# bicyclelab-charger-1.net
KiCad netlist of a schematic drawn in EAGLE
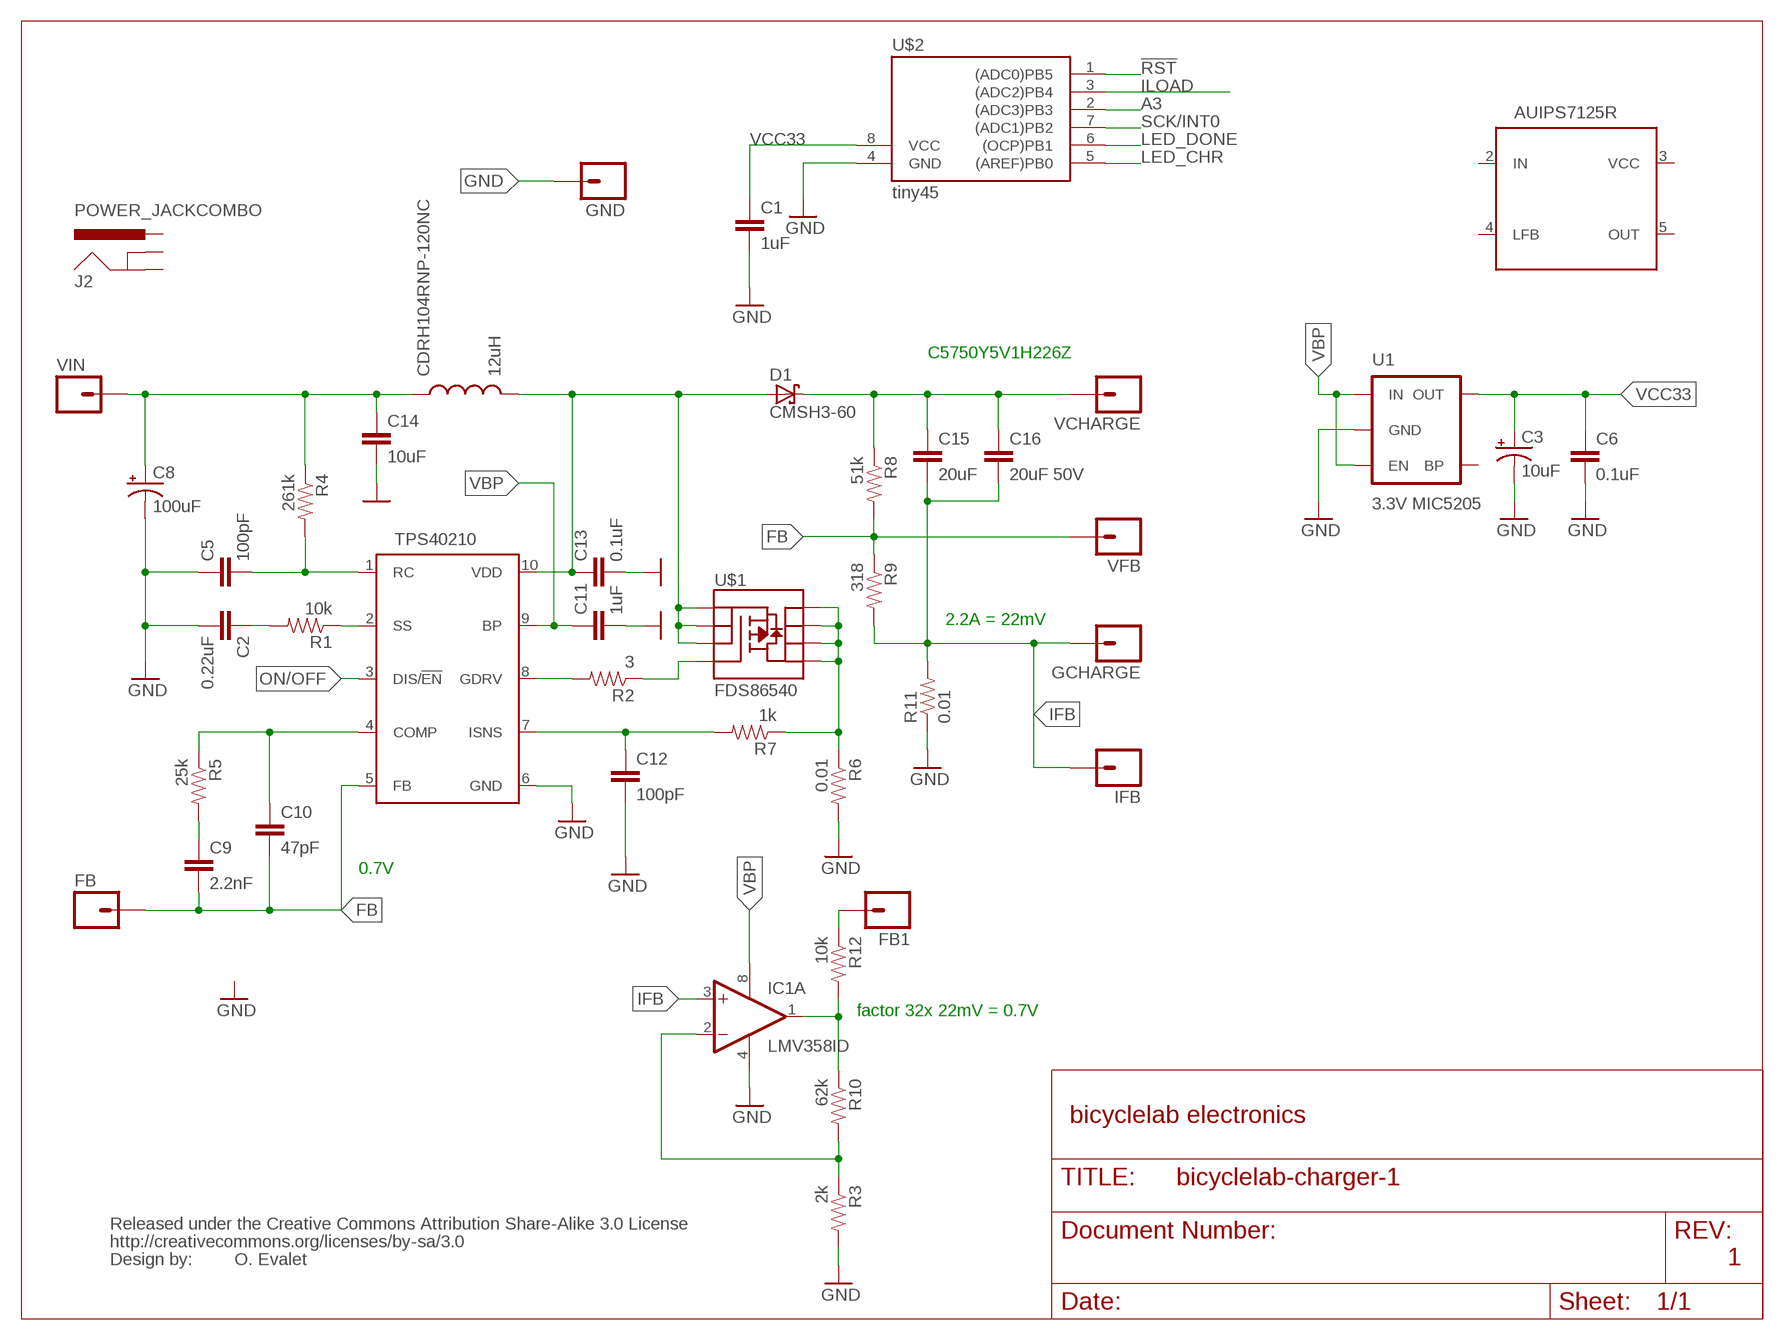
[diagram p0: schematic, sheet 1]

(export (version "E")
  (design (tool "Eeschema 10.0.6"))
  (components
    (comp (ref "11")
      (value "TPS40211")
      (footprint "eagle-import:MSOP-10-GNDPAD")
      (libsource (lib "eagle-import") (part "TPS40210"))
    )
    (comp (ref "C1")
      (value "1uF")
      (footprint "eagle-import:0402-CAP")
      (libsource (lib "eagle-import") (part "SparkFun_CAP0402-CAP"))
    )
    (comp (ref "C2")
      (value "0.22uF")
      (footprint "eagle-import:0402-CAP")
      (libsource (lib "eagle-import") (part "SparkFun_CAP0402-CAP"))
    )
    (comp (ref "C3")
      (value "10uF")
      (footprint "eagle-import:EIA3216")
      (libsource (lib "eagle-import") (part "SparkFun_CAP_POL1206"))
    )
    (comp (ref "C5")
      (value "100pF")
      (footprint "eagle-import:0402-CAP")
      (libsource (lib "eagle-import") (part "SparkFun_CAP0402-CAP"))
    )
    (comp (ref "C6")
      (value "0.1uF")
      (footprint "eagle-import:0603-CAP")
      (libsource (lib "eagle-import") (part "SparkFun_CAP0603-CAP"))
    )
    (comp (ref "C8")
      (value "100uF")
      (footprint "eagle-import:PANASONIC_C")
      (libsource (lib "eagle-import") (part "CAP_POLC"))
    )
    (comp (ref "C9")
      (value "2.2nF")
      (footprint "eagle-import:0402-CAP")
      (libsource (lib "eagle-import") (part "SparkFun_CAP0402-CAP"))
    )
    (comp (ref "C10")
      (value "47pF")
      (footprint "eagle-import:0402-CAP")
      (libsource (lib "eagle-import") (part "SparkFun_CAP0402-CAP"))
    )
    (comp (ref "C11")
      (value "1uF")
      (footprint "eagle-import:0402-CAP")
      (libsource (lib "eagle-import") (part "SparkFun_CAP0402-CAP"))
    )
    (comp (ref "C12")
      (value "100pF")
      (footprint "eagle-import:0402-CAP")
      (libsource (lib "eagle-import") (part "SparkFun_CAP0402-CAP"))
    )
    (comp (ref "C13")
      (value "0.1uF")
      (footprint "eagle-import:0402-CAP")
      (libsource (lib "eagle-import") (part "SparkFun_CAP0402-CAP"))
    )
    (comp (ref "C14")
      (value "10uF")
      (footprint "eagle-import:1206")
      (libsource (lib "eagle-import") (part "CAP1206"))
    )
    (comp (ref "C15")
      (value "20uF")
      (footprint "eagle-import:C2220K")
      (libsource (lib "eagle-import") (part "CAPCAP2220"))
    )
    (comp (ref "C16")
      (value "20uF 50V")
      (footprint "eagle-import:C2220K")
      (libsource (lib "eagle-import") (part "CAPCAP2220"))
    )
    (comp (ref "CDRH104RNP-120NC")
      (value "12uH")
      (footprint "eagle-import:CR75")
      (libsource (lib "eagle-import") (part "INDUCTORCR75"))
    )
    (comp (ref "D1")
      (value "CMSH3-60")
      (footprint "eagle-import:SMC")
      (libsource (lib "eagle-import") (part "MBRS30T32"))
    )
    (comp (ref "FB")
      (value "M01SMDNS")
      (footprint "eagle-import:1X01NS")
      (libsource (lib "eagle-import") (part "M01SMDNS"))
    )
    (comp (ref "FB1")
      (value "M01SMDNS")
      (footprint "eagle-import:1X01NS")
      (libsource (lib "eagle-import") (part "M01SMDNS"))
    )
    (comp (ref "GCHARGE")
      (value "M01SMDNS")
      (footprint "eagle-import:1X01NS")
      (libsource (lib "eagle-import") (part "M01SMDNS"))
    )
    (comp (ref "GND")
      (value "M01SMDNS")
      (footprint "eagle-import:1X01NS")
      (libsource (lib "eagle-import") (part "M01SMDNS"))
    )
    (comp (ref "IC1")
      (value "LMV358ID")
      (footprint "eagle-import:SO08")
      (libsource (lib "eagle-import") (part "MCP602SN"))
    )
    (comp (ref "IFB")
      (value "M01SMDNS")
      (footprint "eagle-import:1X01NS")
      (libsource (lib "eagle-import") (part "M01SMDNS"))
    )
    (comp (ref "J2")
      (value "POWER_JACKCOMBO")
      (footprint "eagle-import:POWER_JACK_COMBO")
      (libsource (lib "eagle-import") (part "POWER_JACKCOMBO"))
    )
    (comp (ref "R1")
      (value "10k")
      (footprint "eagle-import:0402-RES")
      (libsource (lib "eagle-import") (part "RESISTOR0402-RES"))
    )
    (comp (ref "R2")
      (value "3")
      (footprint "eagle-import:0402-RES")
      (libsource (lib "eagle-import") (part "RESISTOR0402-RES"))
    )
    (comp (ref "R3")
      (value "2k")
      (footprint "eagle-import:0402-RES")
      (libsource (lib "eagle-import") (part "RESISTOR0402-RES"))
    )
    (comp (ref "R4")
      (value "261k")
      (footprint "eagle-import:0402-RES")
      (libsource (lib "eagle-import") (part "RESISTOR0402-RES"))
    )
    (comp (ref "R5")
      (value "25k")
      (footprint "eagle-import:0402-RES")
      (libsource (lib "eagle-import") (part "RESISTOR0402-RES"))
    )
    (comp (ref "R6")
      (value "0.01")
      (footprint "eagle-import:0402-RES")
      (libsource (lib "eagle-import") (part "RESISTOR0402-RES"))
    )
    (comp (ref "R7")
      (value "1k")
      (footprint "eagle-import:0402-RES")
      (libsource (lib "eagle-import") (part "RESISTOR0402-RES"))
    )
    (comp (ref "R8")
      (value "51k")
      (footprint "eagle-import:0402-RES")
      (libsource (lib "eagle-import") (part "RESISTOR0402-RES"))
    )
    (comp (ref "R9")
      (value "318")
      (footprint "eagle-import:0402-RES")
      (libsource (lib "eagle-import") (part "RESISTOR0402-RES"))
    )
    (comp (ref "R10")
      (value "62k")
      (footprint "eagle-import:0402-RES")
      (libsource (lib "eagle-import") (part "RESISTOR0402-RES"))
    )
    (comp (ref "R11")
      (value "0.01")
      (footprint "eagle-import:0402-RES")
      (libsource (lib "eagle-import") (part "RESISTOR0402-RES"))
    )
    (comp (ref "R12")
      (value "10k")
      (footprint "eagle-import:0402-RES")
      (libsource (lib "eagle-import") (part "RESISTOR0402-RES"))
    )
    (comp (ref "U$1")
      (value "FDS86540")
      (footprint "eagle-import:SO08")
      (libsource (lib "eagle-import") (part "MOSFET-PCHANNEL-SOIC8SOIC8"))
    )
    (comp (ref "U$2")
      (value "tiny45")
      (footprint "eagle-import:SOIC8")
      (libsource (lib "eagle-import") (part "TINY25/45/85-20SU"))
    )
    (comp (ref "U$5")
      (value "CREATIVE_COMMONS")
      (footprint "eagle-import:CREATIVE_COMMONS")
      (libsource (lib "eagle-import") (part "CREATIVE_COMMONS"))
    )
    (comp (ref "U$8")
      (value "AUIPS7125R")
      (footprint "eagle-import:DPAK-5")
      (libsource (lib "eagle-import") (part "AUIPS7125R"))
    )
    (comp (ref "U1")
      (value "3.3V MIC5205")
      (footprint "eagle-import:SOT23-5")
      (libsource (lib "eagle-import") (part "V_REG_LDOSMD"))
    )
    (comp (ref "VCHARGE")
      (value "M01SMDNS")
      (footprint "eagle-import:1X01NS")
      (libsource (lib "eagle-import") (part "M01SMDNS"))
    )
    (comp (ref "VFB")
      (value "M01SMDNS")
      (footprint "eagle-import:1X01NS")
      (libsource (lib "eagle-import") (part "M01SMDNS"))
    )
    (comp (ref "VIN")
      (value "M01SMDNS")
      (footprint "eagle-import:1X01NS")
      (libsource (lib "eagle-import") (part "M01SMDNS"))
    )
  )
  (nets
    (net (code "1") (name "/A3") (class "Default")
      (node (ref "U$2") (pin "2") (pinfunction "(ADC3)PB3_2") (pintype "bidirectional"))
    )
    (net (code "2") (name "/ILOAD") (class "Default")
      (node (ref "U$2") (pin "3") (pinfunction "(ADC2)PB4_3") (pintype "bidirectional"))
    )
    (net (code "3") (name "/LED_CHR") (class "Default")
      (node (ref "U$2") (pin "5") (pinfunction "(AREF)PB0_5") (pintype "bidirectional"))
    )
    (net (code "4") (name "/LED_DONE") (class "Default")
      (node (ref "U$2") (pin "6") (pinfunction "(OCP)PB1_6") (pintype "bidirectional"))
    )
    (net (code "5") (name "/SCK{slash}INT0") (class "Default")
      (node (ref "U$2") (pin "7") (pinfunction "(ADC1)PB2_7") (pintype "bidirectional"))
    )
    (net (code "6") (name "/~{RST}") (class "Default")
      (node (ref "U$2") (pin "1") (pinfunction "(ADC0)PB5_1") (pintype "bidirectional"))
    )
    (net (code "7") (name "FB") (class "Default")
      (node (ref "11") (pin "5") (pinfunction "FB_5") (pintype "input"))
      (node (ref "C10") (pin "2") (pinfunction "2_2") (pintype "passive"))
      (node (ref "C9") (pin "2") (pinfunction "2_2") (pintype "passive"))
      (node (ref "FB") (pin "1") (pinfunction "1_1") (pintype "passive"))
      (node (ref "R8") (pin "2") (pinfunction "2_2") (pintype "passive"))
      (node (ref "R9") (pin "1") (pinfunction "1_1") (pintype "passive"))
      (node (ref "VFB") (pin "1") (pinfunction "1_1") (pintype "passive"))
    )
    (net (code "8") (name "GND") (class "Default")
      (node (ref "11") (pin "6") (pinfunction "GND_6") (pintype "passive"))
      (node (ref "C1") (pin "2") (pinfunction "2_2") (pintype "passive"))
      (node (ref "C11") (pin "2") (pinfunction "2_2") (pintype "passive"))
      (node (ref "C12") (pin "2") (pinfunction "2_2") (pintype "passive"))
      (node (ref "C13") (pin "2") (pinfunction "2_2") (pintype "passive"))
      (node (ref "C14") (pin "2") (pinfunction "2_2") (pintype "passive"))
      (node (ref "C2") (pin "2") (pinfunction "2_2") (pintype "passive"))
      (node (ref "C3") (pin "C") (pinfunction "-_C") (pintype "passive"))
      (node (ref "C5") (pin "1") (pinfunction "1_1") (pintype "passive"))
      (node (ref "C6") (pin "2") (pinfunction "2_2") (pintype "passive"))
      (node (ref "C8") (pin "-") (pinfunction "-_-") (pintype "passive"))
      (node (ref "GND") (pin "1") (pinfunction "1_1") (pintype "passive"))
      (node (ref "IC1") (pin "4") (pinfunction "V-_4") (pintype "power_in"))
      (node (ref "R11") (pin "1") (pinfunction "1_1") (pintype "passive"))
      (node (ref "R3") (pin "2") (pinfunction "2_2") (pintype "passive"))
      (node (ref "R6") (pin "2") (pinfunction "2_2") (pintype "passive"))
      (node (ref "U$2") (pin "4") (pinfunction "GND_4") (pintype "power_in"))
      (node (ref "U1") (pin "2") (pinfunction "GND_2") (pintype "input"))
    )
    (net (code "9") (name "IFB") (class "Default")
      (node (ref "C15") (pin "2") (pinfunction "2_2") (pintype "passive"))
      (node (ref "C16") (pin "2") (pinfunction "2_2") (pintype "passive"))
      (node (ref "GCHARGE") (pin "1") (pinfunction "1_1") (pintype "passive"))
      (node (ref "IC1") (pin "3") (pinfunction "+IN_3") (pintype "input"))
      (node (ref "IFB") (pin "1") (pinfunction "1_1") (pintype "passive"))
      (node (ref "R11") (pin "2") (pinfunction "2_2") (pintype "passive"))
      (node (ref "R9") (pin "2") (pinfunction "2_2") (pintype "passive"))
    )
    (net (code "10") (name "Net-(11-COMP)") (class "Default")
      (node (ref "11") (pin "4") (pinfunction "COMP_4") (pintype "input"))
      (node (ref "C10") (pin "1") (pinfunction "1_1") (pintype "passive"))
      (node (ref "R5") (pin "1") (pinfunction "1_1") (pintype "passive"))
    )
    (net (code "11") (name "Net-(11-GDRV)") (class "Default")
      (node (ref "11") (pin "8") (pinfunction "GDRV_8") (pintype "passive"))
      (node (ref "R2") (pin "2") (pinfunction "2_2") (pintype "passive"))
    )
    (net (code "12") (name "Net-(11-ISNS)") (class "Default")
      (node (ref "11") (pin "7") (pinfunction "ISNS_7") (pintype "passive"))
      (node (ref "C12") (pin "1") (pinfunction "1_1") (pintype "passive"))
      (node (ref "R7") (pin "2") (pinfunction "2_2") (pintype "passive"))
    )
    (net (code "13") (name "Net-(11-RC)") (class "Default")
      (node (ref "11") (pin "1") (pinfunction "RC_1") (pintype "input"))
      (node (ref "C5") (pin "2") (pinfunction "2_2") (pintype "passive"))
      (node (ref "R4") (pin "2") (pinfunction "2_2") (pintype "passive"))
    )
    (net (code "14") (name "Net-(11-SS)") (class "Default")
      (node (ref "11") (pin "2") (pinfunction "SS_2") (pintype "input"))
      (node (ref "R1") (pin "1") (pinfunction "1_1") (pintype "passive"))
    )
    (net (code "15") (name "Net-(11-VDD)") (class "Default")
      (node (ref "11") (pin "10") (pinfunction "VDD_10") (pintype "passive"))
      (node (ref "C13") (pin "1") (pinfunction "1_1") (pintype "passive"))
      (node (ref "CDRH104RNP-120NC") (pin "P$2") (pinfunction "2_P$2") (pintype "passive"))
      (node (ref "D1") (pin "A") (pinfunction "A_A") (pintype "passive"))
      (node (ref "U$1") (pin "1") (pinfunction "S_1") (pintype "bidirectional"))
      (node (ref "U$1") (pin "2") (pinfunction "S_2") (pintype "bidirectional"))
      (node (ref "U$1") (pin "3") (pinfunction "S_3") (pintype "bidirectional"))
    )
    (net (code "16") (name "Net-(C2-Pad1)") (class "Default")
      (node (ref "C2") (pin "1") (pinfunction "1_1") (pintype "passive"))
      (node (ref "R1") (pin "2") (pinfunction "2_2") (pintype "passive"))
    )
    (net (code "17") (name "Net-(C9-Pad1)") (class "Default")
      (node (ref "C9") (pin "1") (pinfunction "1_1") (pintype "passive"))
      (node (ref "R5") (pin "2") (pinfunction "2_2") (pintype "passive"))
    )
    (net (code "18") (name "Net-(C15-Pad1)") (class "Default")
      (node (ref "C15") (pin "1") (pinfunction "1_1") (pintype "passive"))
      (node (ref "C16") (pin "1") (pinfunction "1_1") (pintype "passive"))
      (node (ref "D1") (pin "C") (pinfunction "C_C") (pintype "passive"))
      (node (ref "R8") (pin "1") (pinfunction "1_1") (pintype "passive"))
      (node (ref "VCHARGE") (pin "1") (pinfunction "1_1") (pintype "passive"))
    )
    (net (code "19") (name "Net-(CDRH104RNP-120NC-1)") (class "Default")
      (node (ref "C14") (pin "1") (pinfunction "1_1") (pintype "passive"))
      (node (ref "C8") (pin "+") (pinfunction "+_+") (pintype "passive"))
      (node (ref "CDRH104RNP-120NC") (pin "P$1") (pinfunction "1_P$1") (pintype "passive"))
      (node (ref "R4") (pin "1") (pinfunction "1_1") (pintype "passive"))
      (node (ref "VIN") (pin "1") (pinfunction "1_1") (pintype "passive"))
    )
    (net (code "20") (name "Net-(FB1-Pad1)") (class "Default")
      (node (ref "FB1") (pin "1") (pinfunction "1_1") (pintype "passive"))
      (node (ref "R12") (pin "1") (pinfunction "1_1") (pintype "passive"))
    )
    (net (code "21") (name "Net-(IC1A--IN)") (class "Default")
      (node (ref "IC1") (pin "2") (pinfunction "-IN_2") (pintype "input"))
      (node (ref "R10") (pin "2") (pinfunction "2_2") (pintype "passive"))
      (node (ref "R3") (pin "1") (pinfunction "1_1") (pintype "passive"))
    )
    (net (code "22") (name "Net-(IC1A-OUT)") (class "Default")
      (node (ref "IC1") (pin "1") (pinfunction "OUT_1") (pintype "output"))
      (node (ref "R10") (pin "1") (pinfunction "1_1") (pintype "passive"))
      (node (ref "R12") (pin "2") (pinfunction "2_2") (pintype "passive"))
    )
    (net (code "23") (name "Net-(R6-Pad1)") (class "Default")
      (node (ref "R6") (pin "1") (pinfunction "1_1") (pintype "passive"))
      (node (ref "R7") (pin "1") (pinfunction "1_1") (pintype "passive"))
      (node (ref "U$1") (pin "5") (pinfunction "D_5") (pintype "bidirectional"))
      (node (ref "U$1") (pin "6") (pinfunction "D_6") (pintype "bidirectional"))
      (node (ref "U$1") (pin "7") (pinfunction "D_7") (pintype "bidirectional"))
      (node (ref "U$1") (pin "8") (pinfunction "D_8") (pintype "bidirectional"))
    )
    (net (code "24") (name "Net-(U$1-G)") (class "Default")
      (node (ref "R2") (pin "1") (pinfunction "1_1") (pintype "passive"))
      (node (ref "U$1") (pin "4") (pinfunction "G_4") (pintype "bidirectional"))
    )
    (net (code "25") (name "ON{slash}OFF") (class "Default")
      (node (ref "11") (pin "3") (pinfunction "DIS/~{EN}_3") (pintype "input"))
    )
    (net (code "26") (name "VBP") (class "Default")
      (node (ref "11") (pin "9") (pinfunction "BP_9") (pintype "passive"))
      (node (ref "C11") (pin "1") (pinfunction "1_1") (pintype "passive"))
      (node (ref "IC1") (pin "8") (pinfunction "V+_8") (pintype "power_in"))
      (node (ref "U1") (pin "1") (pinfunction "IN_1") (pintype "input"))
      (node (ref "U1") (pin "3") (pinfunction "EN_3") (pintype "input"))
    )
    (net (code "27") (name "VCC33") (class "Default")
      (node (ref "C1") (pin "1") (pinfunction "1_1") (pintype "passive"))
      (node (ref "C3") (pin "A") (pinfunction "+_A") (pintype "passive"))
      (node (ref "C6") (pin "1") (pinfunction "1_1") (pintype "passive"))
      (node (ref "U$2") (pin "8") (pinfunction "VCC_8") (pintype "power_in"))
      (node (ref "U1") (pin "5") (pinfunction "OUT_5") (pintype "passive"))
    )
    (net (code "28") (name "unconnected-(11-PadGND)") (class "Default")
      (node (ref "11") (pin "GND") (pinfunction "GND_GND") (pintype "passive"))
    )
    (net (code "29") (name "unconnected-(J2-GND-PadGND@1)") (class "Default")
      (node (ref "J2") (pin "GND@1") (pinfunction "GND_GND@1") (pintype "bidirectional"))
    )
    (net (code "30") (name "unconnected-(J2-GNDBREAK-PadGND)") (class "Default")
      (node (ref "J2") (pin "GND") (pinfunction "GNDBREAK_GND") (pintype "bidirectional"))
    )
    (net (code "31") (name "unconnected-(J2-PWR-PadPOWER)") (class "Default")
      (node (ref "J2") (pin "POWER") (pinfunction "PWR_POWER") (pintype "bidirectional"))
    )
    (net (code "32") (name "unconnected-(U$8-IN-Pad2)") (class "Default")
      (node (ref "U$8") (pin "2") (pinfunction "IN_2") (pintype "input"))
    )
    (net (code "33") (name "unconnected-(U$8-LFB-Pad4)") (class "Default")
      (node (ref "U$8") (pin "4") (pinfunction "LFB_4") (pintype "output"))
    )
    (net (code "34") (name "unconnected-(U$8-NC-Pad1)") (class "Default")
      (node (ref "U$8") (pin "1") (pinfunction "NC_1") (pintype "no_connect"))
    )
    (net (code "35") (name "unconnected-(U$8-OUT-Pad5)") (class "Default")
      (node (ref "U$8") (pin "5") (pinfunction "OUT_5") (pintype "output"))
    )
    (net (code "36") (name "unconnected-(U$8-VCC-Pad3)") (class "Default")
      (node (ref "U$8") (pin "3") (pinfunction "VCC_3") (pintype "input"))
    )
    (net (code "37") (name "unconnected-(U1-BP-Pad4)") (class "Default")
      (node (ref "U1") (pin "4") (pinfunction "BP_4") (pintype "input"))
    )
  )
)
